# power_pre.net
KiCad netlist of a schematic drawn in EAGLE
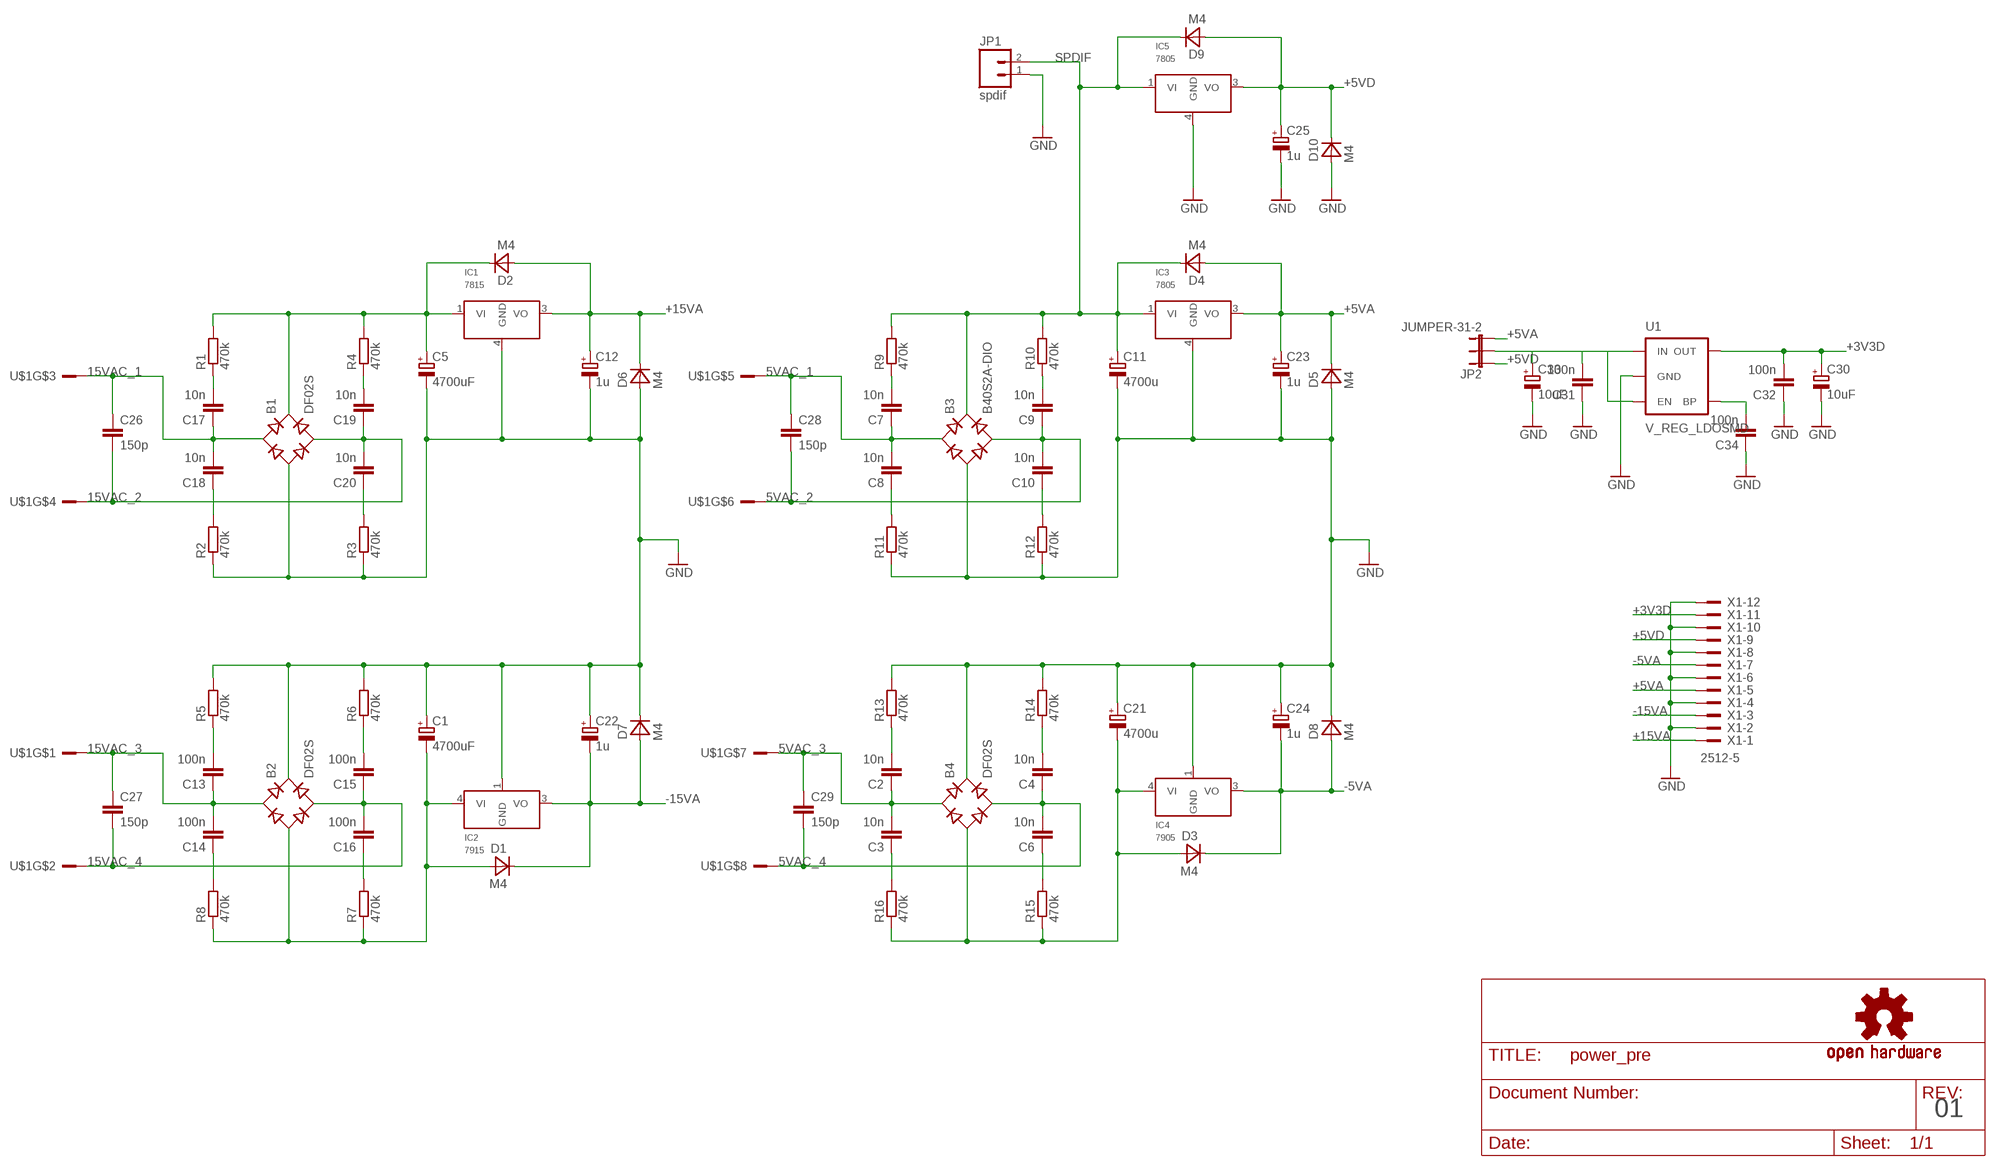
[diagram p0: schematic, sheet 1]

(export (version "E")
  (design (tool "Eeschema 10.0.6"))
  (components
    (comp (ref "B1")
      (value "DF02S")
      (footprint "eagle-import:DFS")
      (libsource (lib "eagle-import") (part "DFS02"))
    )
    (comp (ref "B2")
      (value "DF02S")
      (footprint "eagle-import:DFS")
      (libsource (lib "eagle-import") (part "DFS02"))
    )
    (comp (ref "B3")
      (value "B40S2A-DIO")
      (footprint "eagle-import:DFS")
      (libsource (lib "eagle-import") (part "DFS02"))
    )
    (comp (ref "B4")
      (value "DF02S")
      (footprint "eagle-import:DFS")
      (libsource (lib "eagle-import") (part "DFS02"))
    )
    (comp (ref "C1")
      (value "4700uF")
      (footprint "eagle-import:E7,5-18")
      (libsource (lib "eagle-import") (part "CPOL-EUE7.5-18"))
    )
    (comp (ref "C2")
      (value "10n")
      (footprint "eagle-import:C0805")
      (libsource (lib "eagle-import") (part "C-EUC0805"))
    )
    (comp (ref "C3")
      (value "10n")
      (footprint "eagle-import:C0805")
      (libsource (lib "eagle-import") (part "C-EUC0805"))
    )
    (comp (ref "C4")
      (value "10n")
      (footprint "eagle-import:C0805")
      (libsource (lib "eagle-import") (part "C-EUC0805"))
    )
    (comp (ref "C5")
      (value "4700uF")
      (footprint "eagle-import:E7,5-18")
      (libsource (lib "eagle-import") (part "CPOL-EUE7.5-18"))
    )
    (comp (ref "C6")
      (value "10n")
      (footprint "eagle-import:C0805")
      (libsource (lib "eagle-import") (part "C-EUC0805"))
    )
    (comp (ref "C7")
      (value "10n")
      (footprint "eagle-import:C0805")
      (libsource (lib "eagle-import") (part "C-EUC0805"))
    )
    (comp (ref "C8")
      (value "10n")
      (footprint "eagle-import:C0805")
      (libsource (lib "eagle-import") (part "C-EUC0805"))
    )
    (comp (ref "C9")
      (value "10n")
      (footprint "eagle-import:C0805")
      (libsource (lib "eagle-import") (part "C-EUC0805"))
    )
    (comp (ref "C10")
      (value "10n")
      (footprint "eagle-import:C0805")
      (libsource (lib "eagle-import") (part "C-EUC0805"))
    )
    (comp (ref "C11")
      (value "4700u")
      (footprint "eagle-import:E7,5-16")
      (libsource (lib "eagle-import") (part "CPOL-EUE7.5-16"))
    )
    (comp (ref "C12")
      (value "1u")
      (footprint "eagle-import:PANASONIC_B")
      (libsource (lib "eagle-import") (part "CPOL-EUB"))
    )
    (comp (ref "C13")
      (value "100n")
      (footprint "eagle-import:C0805")
      (libsource (lib "eagle-import") (part "C-EUC0805"))
    )
    (comp (ref "C14")
      (value "100n")
      (footprint "eagle-import:C0805")
      (libsource (lib "eagle-import") (part "C-EUC0805"))
    )
    (comp (ref "C15")
      (value "100n")
      (footprint "eagle-import:C0805")
      (libsource (lib "eagle-import") (part "C-EUC0805"))
    )
    (comp (ref "C16")
      (value "100n")
      (footprint "eagle-import:C0805")
      (libsource (lib "eagle-import") (part "C-EUC0805"))
    )
    (comp (ref "C17")
      (value "10n")
      (footprint "eagle-import:C0805")
      (libsource (lib "eagle-import") (part "C-EUC0805"))
    )
    (comp (ref "C18")
      (value "10n")
      (footprint "eagle-import:C0805")
      (libsource (lib "eagle-import") (part "C-EUC0805"))
    )
    (comp (ref "C19")
      (value "10n")
      (footprint "eagle-import:C0805")
      (libsource (lib "eagle-import") (part "C-EUC0805"))
    )
    (comp (ref "C20")
      (value "10n")
      (footprint "eagle-import:C0805")
      (libsource (lib "eagle-import") (part "C-EUC0805"))
    )
    (comp (ref "C21")
      (value "4700u")
      (footprint "eagle-import:E7,5-16")
      (libsource (lib "eagle-import") (part "CPOL-EUE7.5-16"))
    )
    (comp (ref "C22")
      (value "1u")
      (footprint "eagle-import:PANASONIC_B")
      (libsource (lib "eagle-import") (part "CPOL-EUB"))
    )
    (comp (ref "C23")
      (value "1u")
      (footprint "eagle-import:PANASONIC_B")
      (libsource (lib "eagle-import") (part "CPOL-EUB"))
    )
    (comp (ref "C24")
      (value "1u")
      (footprint "eagle-import:PANASONIC_B")
      (libsource (lib "eagle-import") (part "CPOL-EUB"))
    )
    (comp (ref "C25")
      (value "1u")
      (footprint "eagle-import:PANASONIC_B")
      (libsource (lib "eagle-import") (part "CPOL-EUB"))
    )
    (comp (ref "C26")
      (value "150p")
      (footprint "eagle-import:C5B4.5")
      (libsource (lib "eagle-import") (part "C5/4.5"))
    )
    (comp (ref "C27")
      (value "150p")
      (footprint "eagle-import:C5B4.5")
      (libsource (lib "eagle-import") (part "C5/4.5"))
    )
    (comp (ref "C28")
      (value "150p")
      (footprint "eagle-import:C5B4.5")
      (libsource (lib "eagle-import") (part "C5/4.5"))
    )
    (comp (ref "C29")
      (value "150p")
      (footprint "eagle-import:C5B4.5")
      (libsource (lib "eagle-import") (part "C5/4.5"))
    )
    (comp (ref "C30")
      (value "10uF")
      (footprint "eagle-import:153CLV-0405")
      (libsource (lib "eagle-import") (part "CPOL-EU153CLV-0405"))
    )
    (comp (ref "C31")
      (value "100n")
      (footprint "eagle-import:C0805")
      (libsource (lib "eagle-import") (part "C-EUC0805"))
    )
    (comp (ref "C32")
      (value "100n")
      (footprint "eagle-import:C0805")
      (libsource (lib "eagle-import") (part "C-EUC0805"))
    )
    (comp (ref "C33")
      (value "10uF")
      (footprint "eagle-import:153CLV-0405")
      (libsource (lib "eagle-import") (part "CPOL-EU153CLV-0405"))
    )
    (comp (ref "C34")
      (value "100n")
      (footprint "eagle-import:C0805")
      (libsource (lib "eagle-import") (part "C-EUC0805"))
    )
    (comp (ref "D1")
      (value "M4")
      (footprint "eagle-import:SMA")
      (libsource (lib "eagle-import") (part "MBRA340T3"))
    )
    (comp (ref "D2")
      (value "M4")
      (footprint "eagle-import:SMA")
      (libsource (lib "eagle-import") (part "MBRA340T3"))
    )
    (comp (ref "D3")
      (value "M4")
      (footprint "eagle-import:SMA")
      (libsource (lib "eagle-import") (part "MBRA340T3"))
    )
    (comp (ref "D4")
      (value "M4")
      (footprint "eagle-import:SMA")
      (libsource (lib "eagle-import") (part "MBRA340T3"))
    )
    (comp (ref "D5")
      (value "M4")
      (footprint "eagle-import:SMA")
      (libsource (lib "eagle-import") (part "MBRA340T3"))
    )
    (comp (ref "D6")
      (value "M4")
      (footprint "eagle-import:SMA")
      (libsource (lib "eagle-import") (part "MBRA340T3"))
    )
    (comp (ref "D7")
      (value "M4")
      (footprint "eagle-import:SMA")
      (libsource (lib "eagle-import") (part "MBRA340T3"))
    )
    (comp (ref "D8")
      (value "M4")
      (footprint "eagle-import:SMA")
      (libsource (lib "eagle-import") (part "MBRA340T3"))
    )
    (comp (ref "D9")
      (value "M4")
      (footprint "eagle-import:SMA")
      (libsource (lib "eagle-import") (part "MBRA340T3"))
    )
    (comp (ref "D10")
      (value "M4")
      (footprint "eagle-import:SMA")
      (libsource (lib "eagle-import") (part "MBRA340T3"))
    )
    (comp (ref "IC1")
      (value "7815")
      (footprint "eagle-import:D2PACK")
      (libsource (lib "eagle-import") (part "78XX"))
    )
    (comp (ref "IC2")
      (value "7915")
      (footprint "eagle-import:D2PACK")
      (libsource (lib "eagle-import") (part "79XX"))
    )
    (comp (ref "IC3")
      (value "7805")
      (footprint "eagle-import:D2PACK")
      (libsource (lib "eagle-import") (part "78XX"))
    )
    (comp (ref "IC4")
      (value "7905")
      (footprint "eagle-import:D2PACK")
      (libsource (lib "eagle-import") (part "79XX"))
    )
    (comp (ref "IC5")
      (value "7805")
      (footprint "eagle-import:D2PACK")
      (libsource (lib "eagle-import") (part "78XX"))
    )
    (comp (ref "JP1")
      (value "spdif")
      (footprint "eagle-import:1X02")
      (libsource (lib "eagle-import") (part "M02PTH"))
    )
    (comp (ref "JP2")
      (value "JUMPER-31-2")
      (footprint "eagle-import:SJ_3_PASTE1&2")
      (libsource (lib "eagle-import") (part "JUMPER-31-2"))
    )
    (comp (ref "R1")
      (value "470k")
      (footprint "eagle-import:R0805W")
      (libsource (lib "eagle-import") (part "R-EU_R0805W"))
    )
    (comp (ref "R2")
      (value "470k")
      (footprint "eagle-import:R0805W")
      (libsource (lib "eagle-import") (part "R-EU_R0805W"))
    )
    (comp (ref "R3")
      (value "470k")
      (footprint "eagle-import:R0805W")
      (libsource (lib "eagle-import") (part "R-EU_R0805W"))
    )
    (comp (ref "R4")
      (value "470k")
      (footprint "eagle-import:R0805W")
      (libsource (lib "eagle-import") (part "R-EU_R0805W"))
    )
    (comp (ref "R5")
      (value "470k")
      (footprint "eagle-import:R0805W")
      (libsource (lib "eagle-import") (part "R-EU_R0805W"))
    )
    (comp (ref "R6")
      (value "470k")
      (footprint "eagle-import:R0805W")
      (libsource (lib "eagle-import") (part "R-EU_R0805W"))
    )
    (comp (ref "R7")
      (value "470k")
      (footprint "eagle-import:R0805W")
      (libsource (lib "eagle-import") (part "R-EU_R0805W"))
    )
    (comp (ref "R8")
      (value "470k")
      (footprint "eagle-import:R0805W")
      (libsource (lib "eagle-import") (part "R-EU_R0805W"))
    )
    (comp (ref "R9")
      (value "470k")
      (footprint "eagle-import:R0805W")
      (libsource (lib "eagle-import") (part "R-EU_R0805W"))
    )
    (comp (ref "R10")
      (value "470k")
      (footprint "eagle-import:R0805W")
      (libsource (lib "eagle-import") (part "R-EU_R0805W"))
    )
    (comp (ref "R11")
      (value "470k")
      (footprint "eagle-import:R0805W")
      (libsource (lib "eagle-import") (part "R-EU_R0805W"))
    )
    (comp (ref "R12")
      (value "470k")
      (footprint "eagle-import:R0805W")
      (libsource (lib "eagle-import") (part "R-EU_R0805W"))
    )
    (comp (ref "R13")
      (value "470k")
      (footprint "eagle-import:R0805W")
      (libsource (lib "eagle-import") (part "R-EU_R0805W"))
    )
    (comp (ref "R14")
      (value "470k")
      (footprint "eagle-import:R0805W")
      (libsource (lib "eagle-import") (part "R-EU_R0805W"))
    )
    (comp (ref "R15")
      (value "470k")
      (footprint "eagle-import:R0805W")
      (libsource (lib "eagle-import") (part "R-EU_R0805W"))
    )
    (comp (ref "R16")
      (value "470k")
      (footprint "eagle-import:R0805W")
      (libsource (lib "eagle-import") (part "R-EU_R0805W"))
    )
    (comp (ref "U$1")
      (value "DEGSON_8")
      (footprint "eagle-import:DEGSON_8")
      (libsource (lib "eagle-import") (part "DEGSON_8"))
    )
    (comp (ref "U$7")
      (value "OSHW-LOGOM")
      (footprint "eagle-import:OSHW-LOGO-M")
      (libsource (lib "eagle-import") (part "OSHW-LOGOM"))
    )
    (comp (ref "U1")
      (value "V_REG_LDOSMD")
      (footprint "eagle-import:SOT23-5")
      (libsource (lib "eagle-import") (part "V_REG_LDOSMD"))
    )
    (comp (ref "X1")
      (value "2512-5")
      (footprint "eagle-import:PAK100_2500-5-12")
      (fields (field (name "MPN") "N2514-5002RB"))
      (libsource (lib "eagle-import") (part "2512-5"))
    )
  )
  (nets
    (net (code "1") (name "/+3V3D") (class "Default")
      (node (ref "C30") (pin "+") (pinfunction "+_+") (pintype "passive"))
      (node (ref "C32") (pin "2") (pinfunction "2_2") (pintype "passive"))
      (node (ref "U1") (pin "5") (pinfunction "OUT_5") (pintype "passive"))
      (node (ref "X1") (pin "11") (pinfunction "KL_11") (pintype "passive"))
    )
    (net (code "2") (name "/+5VA") (class "Default")
      (node (ref "C23") (pin "+") (pinfunction "+_+") (pintype "passive"))
      (node (ref "D4") (pin "A") (pinfunction "A_A") (pintype "passive"))
      (node (ref "D5") (pin "C") (pinfunction "C_C") (pintype "passive"))
      (node (ref "IC3") (pin "3") (pinfunction "VO_3") (pintype "bidirectional"))
      (node (ref "JP2") (pin "3") (pinfunction "3_3") (pintype "passive"))
      (node (ref "X1") (pin "5") (pinfunction "KL_5") (pintype "passive"))
    )
    (net (code "3") (name "/+5VD") (class "Default")
      (node (ref "C25") (pin "+") (pinfunction "+_+") (pintype "passive"))
      (node (ref "D10") (pin "C") (pinfunction "C_C") (pintype "passive"))
      (node (ref "D9") (pin "A") (pinfunction "A_A") (pintype "passive"))
      (node (ref "IC5") (pin "3") (pinfunction "VO_3") (pintype "bidirectional"))
      (node (ref "JP2") (pin "1") (pinfunction "1_1") (pintype "passive"))
      (node (ref "X1") (pin "9") (pinfunction "KL_9") (pintype "passive"))
    )
    (net (code "4") (name "/+15VA") (class "Default")
      (node (ref "C12") (pin "+") (pinfunction "+_+") (pintype "passive"))
      (node (ref "D2") (pin "A") (pinfunction "A_A") (pintype "passive"))
      (node (ref "D6") (pin "C") (pinfunction "C_C") (pintype "passive"))
      (node (ref "IC1") (pin "3") (pinfunction "VO_3") (pintype "bidirectional"))
      (node (ref "X1") (pin "1") (pinfunction "KL_1") (pintype "passive"))
    )
    (net (code "5") (name "/-5VA") (class "Default")
      (node (ref "C24") (pin "-") (pinfunction "-_-") (pintype "passive"))
      (node (ref "D3") (pin "C") (pinfunction "C_C") (pintype "passive"))
      (node (ref "D8") (pin "A") (pinfunction "A_A") (pintype "passive"))
      (node (ref "IC4") (pin "3") (pinfunction "VO_3") (pintype "bidirectional"))
      (node (ref "X1") (pin "7") (pinfunction "KL_7") (pintype "passive"))
    )
    (net (code "6") (name "/-15VA") (class "Default")
      (node (ref "C22") (pin "-") (pinfunction "-_-") (pintype "passive"))
      (node (ref "D1") (pin "C") (pinfunction "C_C") (pintype "passive"))
      (node (ref "D7") (pin "A") (pinfunction "A_A") (pintype "passive"))
      (node (ref "IC2") (pin "3") (pinfunction "VO_3") (pintype "bidirectional"))
      (node (ref "X1") (pin "3") (pinfunction "KL_3") (pintype "passive"))
    )
    (net (code "7") (name "/5VAC_1") (class "Default")
      (node (ref "B3") (pin "AC1") (pinfunction "AC1_AC1") (pintype "passive"))
      (node (ref "C28") (pin "1") (pinfunction "1_1") (pintype "passive"))
      (node (ref "C7") (pin "1") (pinfunction "1_1") (pintype "passive"))
      (node (ref "C8") (pin "2") (pinfunction "2_2") (pintype "passive"))
      (node (ref "U$1") (pin "5") (pinfunction "KL_5") (pintype "passive"))
    )
    (net (code "8") (name "/5VAC_2") (class "Default")
      (node (ref "B3") (pin "AC2") (pinfunction "AC2_AC2") (pintype "passive"))
      (node (ref "C10") (pin "2") (pinfunction "2_2") (pintype "passive"))
      (node (ref "C28") (pin "2") (pinfunction "2_2") (pintype "passive"))
      (node (ref "C9") (pin "1") (pinfunction "1_1") (pintype "passive"))
      (node (ref "U$1") (pin "6") (pinfunction "KL_6") (pintype "passive"))
    )
    (net (code "9") (name "/5VAC_3") (class "Default")
      (node (ref "B4") (pin "AC1") (pinfunction "AC1_AC1") (pintype "passive"))
      (node (ref "C2") (pin "1") (pinfunction "1_1") (pintype "passive"))
      (node (ref "C29") (pin "1") (pinfunction "1_1") (pintype "passive"))
      (node (ref "C3") (pin "2") (pinfunction "2_2") (pintype "passive"))
      (node (ref "U$1") (pin "7") (pinfunction "KL_7") (pintype "passive"))
    )
    (net (code "10") (name "/5VAC_4") (class "Default")
      (node (ref "B4") (pin "AC2") (pinfunction "AC2_AC2") (pintype "passive"))
      (node (ref "C29") (pin "2") (pinfunction "2_2") (pintype "passive"))
      (node (ref "C4") (pin "1") (pinfunction "1_1") (pintype "passive"))
      (node (ref "C6") (pin "2") (pinfunction "2_2") (pintype "passive"))
      (node (ref "U$1") (pin "8") (pinfunction "KL_8") (pintype "passive"))
    )
    (net (code "11") (name "/15VAC_1") (class "Default")
      (node (ref "B1") (pin "AC1") (pinfunction "AC1_AC1") (pintype "passive"))
      (node (ref "C17") (pin "1") (pinfunction "1_1") (pintype "passive"))
      (node (ref "C18") (pin "2") (pinfunction "2_2") (pintype "passive"))
      (node (ref "C26") (pin "1") (pinfunction "1_1") (pintype "passive"))
      (node (ref "U$1") (pin "3") (pinfunction "KL_3") (pintype "passive"))
    )
    (net (code "12") (name "/15VAC_2") (class "Default")
      (node (ref "B1") (pin "AC2") (pinfunction "AC2_AC2") (pintype "passive"))
      (node (ref "C19") (pin "1") (pinfunction "1_1") (pintype "passive"))
      (node (ref "C20") (pin "2") (pinfunction "2_2") (pintype "passive"))
      (node (ref "C26") (pin "2") (pinfunction "2_2") (pintype "passive"))
      (node (ref "U$1") (pin "4") (pinfunction "KL_4") (pintype "passive"))
    )
    (net (code "13") (name "/15VAC_3") (class "Default")
      (node (ref "B2") (pin "AC1") (pinfunction "AC1_AC1") (pintype "passive"))
      (node (ref "C13") (pin "1") (pinfunction "1_1") (pintype "passive"))
      (node (ref "C14") (pin "2") (pinfunction "2_2") (pintype "passive"))
      (node (ref "C27") (pin "1") (pinfunction "1_1") (pintype "passive"))
      (node (ref "U$1") (pin "1") (pinfunction "KL_1") (pintype "passive"))
    )
    (net (code "14") (name "/15VAC_4") (class "Default")
      (node (ref "B2") (pin "AC2") (pinfunction "AC2_AC2") (pintype "passive"))
      (node (ref "C15") (pin "1") (pinfunction "1_1") (pintype "passive"))
      (node (ref "C16") (pin "2") (pinfunction "2_2") (pintype "passive"))
      (node (ref "C27") (pin "2") (pinfunction "2_2") (pintype "passive"))
      (node (ref "U$1") (pin "2") (pinfunction "KL_2") (pintype "passive"))
    )
    (net (code "15") (name "/SPDIF") (class "Default")
      (node (ref "B3") (pin "+") (pinfunction "+_+") (pintype "passive"))
      (node (ref "C11") (pin "+") (pinfunction "+_+") (pintype "passive"))
      (node (ref "D4") (pin "C") (pinfunction "C_C") (pintype "passive"))
      (node (ref "D9") (pin "C") (pinfunction "C_C") (pintype "passive"))
      (node (ref "IC3") (pin "1") (pinfunction "VI_1") (pintype "bidirectional"))
      (node (ref "IC5") (pin "1") (pinfunction "VI_1") (pintype "bidirectional"))
      (node (ref "JP1") (pin "2") (pinfunction "2_2") (pintype "passive"))
      (node (ref "R10") (pin "2") (pinfunction "2_2") (pintype "passive"))
      (node (ref "R9") (pin "2") (pinfunction "2_2") (pintype "passive"))
    )
    (net (code "16") (name "GND") (class "Default")
      (node (ref "B1") (pin "-") (pinfunction "-_-") (pintype "passive"))
      (node (ref "B2") (pin "+") (pinfunction "+_+") (pintype "passive"))
      (node (ref "B3") (pin "-") (pinfunction "-_-") (pintype "passive"))
      (node (ref "B4") (pin "+") (pinfunction "+_+") (pintype "passive"))
      (node (ref "C1") (pin "+") (pinfunction "+_+") (pintype "passive"))
      (node (ref "C11") (pin "-") (pinfunction "-_-") (pintype "passive"))
      (node (ref "C12") (pin "-") (pinfunction "-_-") (pintype "passive"))
      (node (ref "C21") (pin "+") (pinfunction "+_+") (pintype "passive"))
      (node (ref "C22") (pin "+") (pinfunction "+_+") (pintype "passive"))
      (node (ref "C23") (pin "-") (pinfunction "-_-") (pintype "passive"))
      (node (ref "C24") (pin "+") (pinfunction "+_+") (pintype "passive"))
      (node (ref "C25") (pin "-") (pinfunction "-_-") (pintype "passive"))
      (node (ref "C30") (pin "-") (pinfunction "-_-") (pintype "passive"))
      (node (ref "C31") (pin "1") (pinfunction "1_1") (pintype "passive"))
      (node (ref "C32") (pin "1") (pinfunction "1_1") (pintype "passive"))
      (node (ref "C33") (pin "-") (pinfunction "-_-") (pintype "passive"))
      (node (ref "C34") (pin "1") (pinfunction "1_1") (pintype "passive"))
      (node (ref "C5") (pin "-") (pinfunction "-_-") (pintype "passive"))
      (node (ref "D10") (pin "A") (pinfunction "A_A") (pintype "passive"))
      (node (ref "D5") (pin "A") (pinfunction "A_A") (pintype "passive"))
      (node (ref "D6") (pin "A") (pinfunction "A_A") (pintype "passive"))
      (node (ref "D7") (pin "C") (pinfunction "C_C") (pintype "passive"))
      (node (ref "D8") (pin "C") (pinfunction "C_C") (pintype "passive"))
      (node (ref "IC1") (pin "4") (pinfunction "GND_4") (pintype "bidirectional"))
      (node (ref "IC2") (pin "1") (pinfunction "GND_1") (pintype "bidirectional"))
      (node (ref "IC3") (pin "4") (pinfunction "GND_4") (pintype "bidirectional"))
      (node (ref "IC4") (pin "1") (pinfunction "GND_1") (pintype "bidirectional"))
      (node (ref "IC5") (pin "4") (pinfunction "GND_4") (pintype "bidirectional"))
      (node (ref "JP1") (pin "1") (pinfunction "1_1") (pintype "passive"))
      (node (ref "R11") (pin "1") (pinfunction "1_1") (pintype "passive"))
      (node (ref "R12") (pin "1") (pinfunction "1_1") (pintype "passive"))
      (node (ref "R13") (pin "2") (pinfunction "2_2") (pintype "passive"))
      (node (ref "R14") (pin "2") (pinfunction "2_2") (pintype "passive"))
      (node (ref "R2") (pin "1") (pinfunction "1_1") (pintype "passive"))
      (node (ref "R3") (pin "1") (pinfunction "1_1") (pintype "passive"))
      (node (ref "R5") (pin "2") (pinfunction "2_2") (pintype "passive"))
      (node (ref "R6") (pin "2") (pinfunction "2_2") (pintype "passive"))
      (node (ref "U1") (pin "2") (pinfunction "GND_2") (pintype "input"))
      (node (ref "X1") (pin "10") (pinfunction "KL_10") (pintype "passive"))
      (node (ref "X1") (pin "12") (pinfunction "KL_12") (pintype "passive"))
      (node (ref "X1") (pin "2") (pinfunction "KL_2") (pintype "passive"))
      (node (ref "X1") (pin "4") (pinfunction "KL_4") (pintype "passive"))
      (node (ref "X1") (pin "6") (pinfunction "KL_6") (pintype "passive"))
      (node (ref "X1") (pin "8") (pinfunction "KL_8") (pintype "passive"))
    )
    (net (code "17") (name "Net-(C2-Pad2)") (class "Default")
      (node (ref "C2") (pin "2") (pinfunction "2_2") (pintype "passive"))
      (node (ref "R13") (pin "1") (pinfunction "1_1") (pintype "passive"))
    )
    (net (code "18") (name "Net-(C3-Pad1)") (class "Default")
      (node (ref "C3") (pin "1") (pinfunction "1_1") (pintype "passive"))
      (node (ref "R16") (pin "2") (pinfunction "2_2") (pintype "passive"))
    )
    (net (code "19") (name "Net-(C4-Pad2)") (class "Default")
      (node (ref "C4") (pin "2") (pinfunction "2_2") (pintype "passive"))
      (node (ref "R14") (pin "1") (pinfunction "1_1") (pintype "passive"))
    )
    (net (code "20") (name "Net-(C6-Pad1)") (class "Default")
      (node (ref "C6") (pin "1") (pinfunction "1_1") (pintype "passive"))
      (node (ref "R15") (pin "2") (pinfunction "2_2") (pintype "passive"))
    )
    (net (code "21") (name "Net-(C7-Pad2)") (class "Default")
      (node (ref "C7") (pin "2") (pinfunction "2_2") (pintype "passive"))
      (node (ref "R9") (pin "1") (pinfunction "1_1") (pintype "passive"))
    )
    (net (code "22") (name "Net-(C8-Pad1)") (class "Default")
      (node (ref "C8") (pin "1") (pinfunction "1_1") (pintype "passive"))
      (node (ref "R11") (pin "2") (pinfunction "2_2") (pintype "passive"))
    )
    (net (code "23") (name "Net-(C9-Pad2)") (class "Default")
      (node (ref "C9") (pin "2") (pinfunction "2_2") (pintype "passive"))
      (node (ref "R10") (pin "1") (pinfunction "1_1") (pintype "passive"))
    )
    (net (code "24") (name "Net-(C10-Pad1)") (class "Default")
      (node (ref "C10") (pin "1") (pinfunction "1_1") (pintype "passive"))
      (node (ref "R12") (pin "2") (pinfunction "2_2") (pintype "passive"))
    )
    (net (code "25") (name "Net-(C13-Pad2)") (class "Default")
      (node (ref "C13") (pin "2") (pinfunction "2_2") (pintype "passive"))
      (node (ref "R5") (pin "1") (pinfunction "1_1") (pintype "passive"))
    )
    (net (code "26") (name "Net-(C14-Pad1)") (class "Default")
      (node (ref "C14") (pin "1") (pinfunction "1_1") (pintype "passive"))
      (node (ref "R8") (pin "2") (pinfunction "2_2") (pintype "passive"))
    )
    (net (code "27") (name "Net-(C15-Pad2)") (class "Default")
      (node (ref "C15") (pin "2") (pinfunction "2_2") (pintype "passive"))
      (node (ref "R6") (pin "1") (pinfunction "1_1") (pintype "passive"))
    )
    (net (code "28") (name "Net-(C16-Pad1)") (class "Default")
      (node (ref "C16") (pin "1") (pinfunction "1_1") (pintype "passive"))
      (node (ref "R7") (pin "2") (pinfunction "2_2") (pintype "passive"))
    )
    (net (code "29") (name "Net-(C17-Pad2)") (class "Default")
      (node (ref "C17") (pin "2") (pinfunction "2_2") (pintype "passive"))
      (node (ref "R1") (pin "1") (pinfunction "1_1") (pintype "passive"))
    )
    (net (code "30") (name "Net-(C18-Pad1)") (class "Default")
      (node (ref "C18") (pin "1") (pinfunction "1_1") (pintype "passive"))
      (node (ref "R2") (pin "2") (pinfunction "2_2") (pintype "passive"))
    )
    (net (code "31") (name "Net-(C19-Pad2)") (class "Default")
      (node (ref "C19") (pin "2") (pinfunction "2_2") (pintype "passive"))
      (node (ref "R4") (pin "1") (pinfunction "1_1") (pintype "passive"))
    )
    (net (code "32") (name "Net-(C20-Pad1)") (class "Default")
      (node (ref "C20") (pin "1") (pinfunction "1_1") (pintype "passive"))
      (node (ref "R3") (pin "2") (pinfunction "2_2") (pintype "passive"))
    )
    (net (code "33") (name "Net-(IC1-VI)") (class "Default")
      (node (ref "B1") (pin "+") (pinfunction "+_+") (pintype "passive"))
      (node (ref "C5") (pin "+") (pinfunction "+_+") (pintype "passive"))
      (node (ref "D2") (pin "C") (pinfunction "C_C") (pintype "passive"))
      (node (ref "IC1") (pin "1") (pinfunction "VI_1") (pintype "bidirectional"))
      (node (ref "R1") (pin "2") (pinfunction "2_2") (pintype "passive"))
      (node (ref "R4") (pin "2") (pinfunction "2_2") (pintype "passive"))
    )
    (net (code "34") (name "Net-(IC2-VI)") (class "Default")
      (node (ref "B2") (pin "-") (pinfunction "-_-") (pintype "passive"))
      (node (ref "C1") (pin "-") (pinfunction "-_-") (pintype "passive"))
      (node (ref "D1") (pin "A") (pinfunction "A_A") (pintype "passive"))
      (node (ref "IC2") (pin "4") (pinfunction "VI_4") (pintype "bidirectional"))
      (node (ref "R7") (pin "1") (pinfunction "1_1") (pintype "passive"))
      (node (ref "R8") (pin "1") (pinfunction "1_1") (pintype "passive"))
    )
    (net (code "35") (name "Net-(IC4-VI)") (class "Default")
      (node (ref "B4") (pin "-") (pinfunction "-_-") (pintype "passive"))
      (node (ref "C21") (pin "-") (pinfunction "-_-") (pintype "passive"))
      (node (ref "D3") (pin "A") (pinfunction "A_A") (pintype "passive"))
      (node (ref "IC4") (pin "4") (pinfunction "VI_4") (pintype "bidirectional"))
      (node (ref "R15") (pin "1") (pinfunction "1_1") (pintype "passive"))
      (node (ref "R16") (pin "1") (pinfunction "1_1") (pintype "passive"))
    )
    (net (code "36") (name "Net-(U1-BP)") (class "Default")
      (node (ref "C34") (pin "2") (pinfunction "2_2") (pintype "passive"))
      (node (ref "U1") (pin "4") (pinfunction "BP_4") (pintype "input"))
    )
    (net (code "37") (name "Net-(U1-EN)") (class "Default")
      (node (ref "C31") (pin "2") (pinfunction "2_2") (pintype "passive"))
      (node (ref "C33") (pin "+") (pinfunction "+_+") (pintype "passive"))
      (node (ref "JP2") (pin "2") (pinfunction "2_2") (pintype "passive"))
      (node (ref "U1") (pin "1") (pinfunction "IN_1") (pintype "input"))
      (node (ref "U1") (pin "3") (pinfunction "EN_3") (pintype "input"))
    )
  )
)
